# Component_Switch.net
KiCad netlist of a schematic drawn in Altium Designer
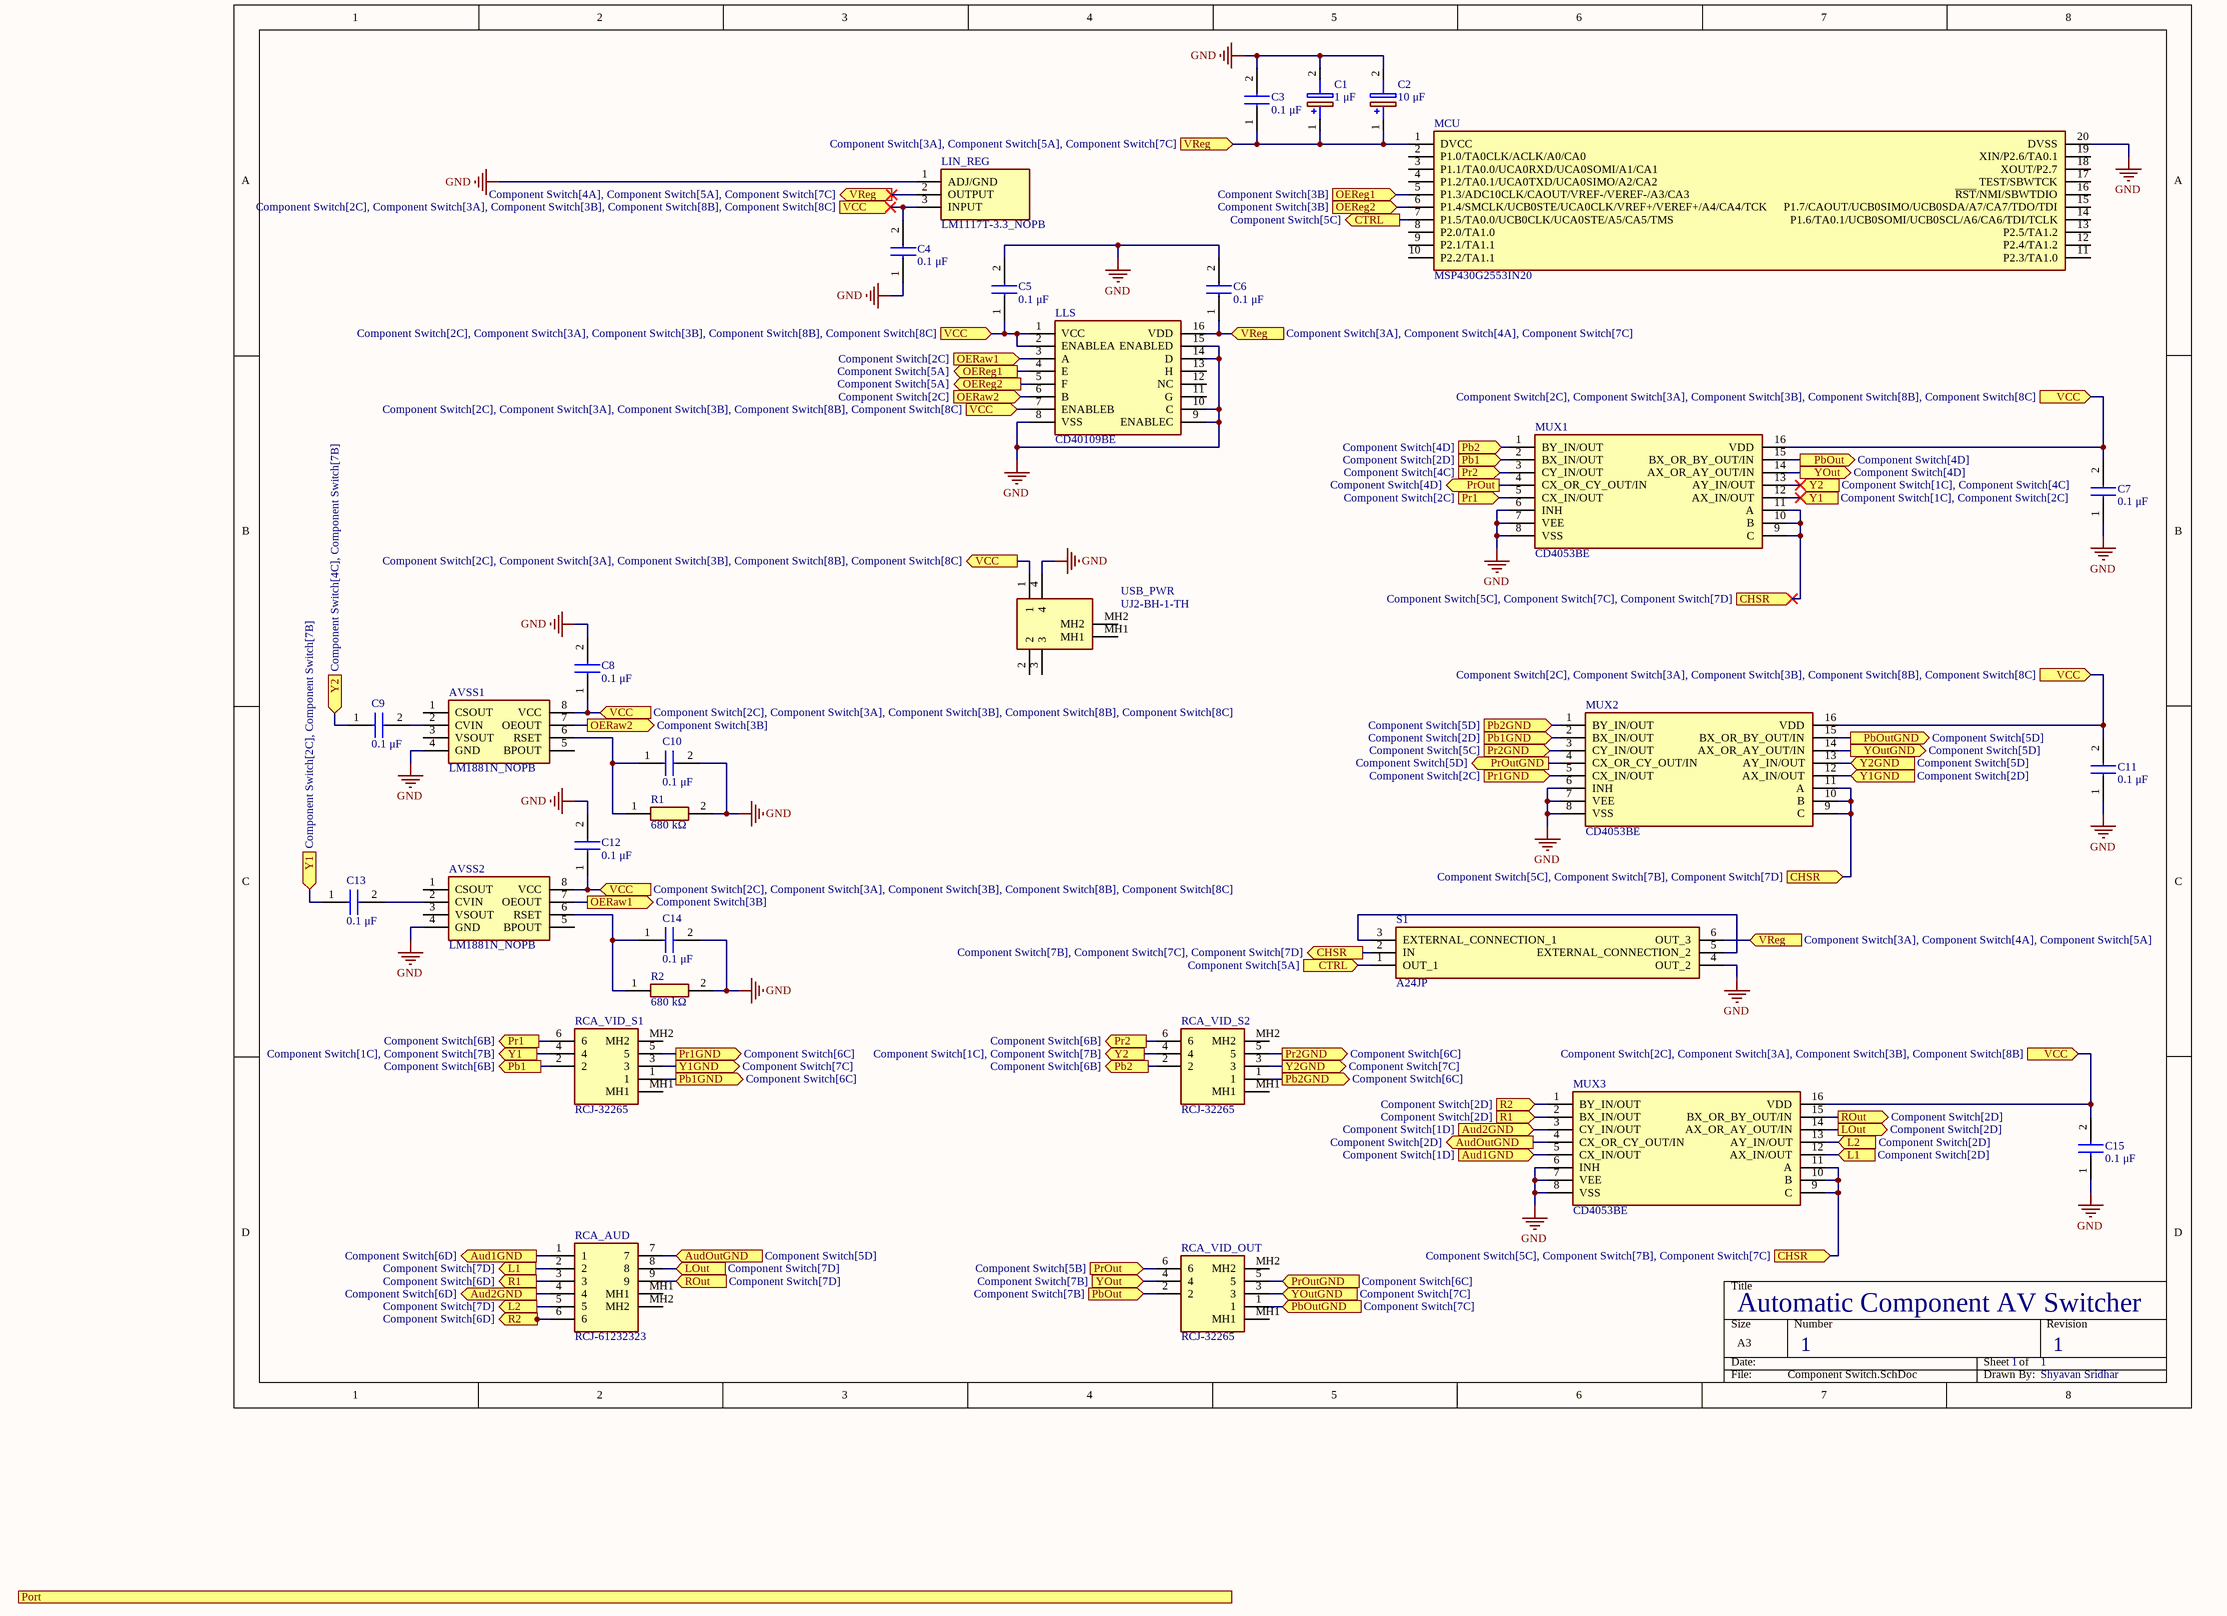
[diagram p0: Component Switch.SchDoc]

(export (version "E")
  (design (tool "Eeschema 10.0.6"))
  (components
    (comp (ref "AVSS1")
      (value "LM1881N_NOPB")
      (footprint "SamacSys:DIP794W53P254L959H508Q8N")
      (description "Integrated Circuit")
      (fields
        (field (name "MANUFACTURER_PART_NUMBER") "LM1881N/NOPB")
        (field (name "MOUSER PART NUMBER") "926-LM1881N/NOPB")
      )
      (libsource (lib "*") (part "LM1881N_NOPB"))
    )
    (comp (ref "AVSS2")
      (value "LM1881N_NOPB")
      (footprint "SamacSys:DIP794W53P254L959H508Q8N")
      (description "Integrated Circuit")
      (fields
        (field (name "MANUFACTURER_PART_NUMBER") "LM1881N/NOPB")
        (field (name "MOUSER PART NUMBER") "926-LM1881N/NOPB")
      )
      (libsource (lib "*") (part "LM1881N_NOPB"))
    )
    (comp (ref "C1")
      (value "1 μF")
      (footprint "SamacSys:CAPPRD200W52D500H1250")
      (description "Capacitor Polarised")
      (fields
        (field (name "MANUFACTURER_PART_NUMBER") "860020672005")
        (field (name "MOUSER PART NUMBER") "710-860020672005")
      )
      (libsource (lib "*") (part "860020672005"))
    )
    (comp (ref "C2")
      (value "10 μF")
      (footprint "SamacSys:CAPPRD200W52D500H1250")
      (description "Capacitor Polarised")
      (fields
        (field (name "MANUFACTURER_PART_NUMBER") "860020472003")
        (field (name "MOUSER PART NUMBER") "710-860020472003")
      )
      (libsource (lib "*") (part "860020472003"))
    )
    (comp (ref "C3")
      (value "0.1 μF")
      (footprint "SamacSys:C320C104K5R5TA")
      (description "Capacitor")
      (fields
        (field (name "MANUFACTURER_PART_NUMBER") "C320C104K5R5TA")
        (field (name "MOUSER PART NUMBER") "80-C320C104K5R")
      )
      (libsource (lib "*") (part "C320C104K5R5TA"))
    )
    (comp (ref "C4")
      (value "0.1 μF")
      (footprint "SamacSys:C320C104K5R5TA")
      (description "Capacitor")
      (fields
        (field (name "MANUFACTURER_PART_NUMBER") "C320C104K5R5TA")
        (field (name "MOUSER PART NUMBER") "80-C320C104K5R")
      )
      (libsource (lib "*") (part "C320C104K5R5TA"))
    )
    (comp (ref "C5")
      (value "0.1 μF")
      (footprint "SamacSys:C320C104K5R5TA")
      (description "Capacitor")
      (fields
        (field (name "MANUFACTURER_PART_NUMBER") "C320C104K5R5TA")
        (field (name "MOUSER PART NUMBER") "80-C320C104K5R")
      )
      (libsource (lib "*") (part "C320C104K5R5TA"))
    )
    (comp (ref "C6")
      (value "0.1 μF")
      (footprint "SamacSys:C320C104K5R5TA")
      (description "Capacitor")
      (fields
        (field (name "MANUFACTURER_PART_NUMBER") "C320C104K5R5TA")
        (field (name "MOUSER PART NUMBER") "80-C320C104K5R")
      )
      (libsource (lib "*") (part "C320C104K5R5TA"))
    )
    (comp (ref "C7")
      (value "0.1 μF")
      (footprint "SamacSys:C320C104K5R5TA")
      (description "Capacitor")
      (fields
        (field (name "MANUFACTURER_PART_NUMBER") "C320C104K5R5TA")
        (field (name "MOUSER PART NUMBER") "80-C320C104K5R")
      )
      (libsource (lib "*") (part "C320C104K5R5TA"))
    )
    (comp (ref "C8")
      (value "0.1 μF")
      (footprint "SamacSys:C320C104K5R5TA")
      (description "Capacitor")
      (fields
        (field (name "MANUFACTURER_PART_NUMBER") "C320C104K5R5TA")
        (field (name "MOUSER PART NUMBER") "80-C320C104K5R")
      )
      (libsource (lib "*") (part "C320C104K5R5TA"))
    )
    (comp (ref "C9")
      (value "0.1 μF")
      (footprint "SamacSys:C320C104K5R5TA")
      (description "Capacitor")
      (fields
        (field (name "MANUFACTURER_PART_NUMBER") "C320C104K5R5TA")
        (field (name "MOUSER PART NUMBER") "80-C320C104K5R")
      )
      (libsource (lib "*") (part "C320C104K5R5TA"))
    )
    (comp (ref "C10")
      (value "0.1 μF")
      (footprint "SamacSys:C320C104K5R5TA")
      (description "Capacitor")
      (fields
        (field (name "MANUFACTURER_PART_NUMBER") "C320C104K5R5TA")
        (field (name "MOUSER PART NUMBER") "80-C320C104K5R")
      )
      (libsource (lib "*") (part "C320C104K5R5TA"))
    )
    (comp (ref "C11")
      (value "0.1 μF")
      (footprint "SamacSys:C320C104K5R5TA")
      (description "Capacitor")
      (fields
        (field (name "MANUFACTURER_PART_NUMBER") "C320C104K5R5TA")
        (field (name "MOUSER PART NUMBER") "80-C320C104K5R")
      )
      (libsource (lib "*") (part "C320C104K5R5TA"))
    )
    (comp (ref "C12")
      (value "0.1 μF")
      (footprint "SamacSys:C320C104K5R5TA")
      (description "Capacitor")
      (fields
        (field (name "MANUFACTURER_PART_NUMBER") "C320C104K5R5TA")
        (field (name "MOUSER PART NUMBER") "80-C320C104K5R")
      )
      (libsource (lib "*") (part "C320C104K5R5TA"))
    )
    (comp (ref "C13")
      (value "0.1 μF")
      (footprint "SamacSys:C320C104K5R5TA")
      (description "Capacitor")
      (fields
        (field (name "MANUFACTURER_PART_NUMBER") "C320C104K5R5TA")
        (field (name "MOUSER PART NUMBER") "80-C320C104K5R")
      )
      (libsource (lib "*") (part "C320C104K5R5TA"))
    )
    (comp (ref "C14")
      (value "0.1 μF")
      (footprint "SamacSys:C320C104K5R5TA")
      (description "Capacitor")
      (fields
        (field (name "MANUFACTURER_PART_NUMBER") "C320C104K5R5TA")
        (field (name "MOUSER PART NUMBER") "80-C320C104K5R")
      )
      (libsource (lib "*") (part "C320C104K5R5TA"))
    )
    (comp (ref "C15")
      (value "0.1 μF")
      (footprint "SamacSys:C320C104K5R5TA")
      (description "Capacitor")
      (fields
        (field (name "MANUFACTURER_PART_NUMBER") "C320C104K5R5TA")
        (field (name "MOUSER PART NUMBER") "80-C320C104K5R")
      )
      (libsource (lib "*") (part "C320C104K5R5TA"))
    )
    (comp (ref "LIN_REG")
      (value "LM1117T-3.3_NOPB")
      (footprint "SamacSys:TO254P470X1028X1955-3P")
      (description "Integrated Circuit")
      (fields
        (field (name "MANUFACTURER_PART_NUMBER") "LM1117T-3.3/NOPB")
        (field (name "MOUSER PART NUMBER") "926-LM1117T-3.3/NOPB")
      )
      (libsource (lib "*") (part "LM1117T-3.3_NOPB"))
    )
    (comp (ref "LLS")
      (value "CD40109BE")
      (footprint "SamacSys:DIP794W53P254L1930H508Q16N")
      (description "Integrated Circuit")
      (fields (field (name "MOUSER PART NUMBER") "595-CD40109BE"))
      (libsource (lib "*") (part "CD40109BE"))
    )
    (comp (ref "MCU")
      (value "MSP430G2553IN20")
      (footprint "SamacSys:DIP794W53P254L2540H508Q20N")
      (description "Integrated Circuit")
      (fields (field (name "MOUSER PART NUMBER") "595-MSP430G2553IN20"))
      (libsource (lib "*") (part "MSP430G2553IN20"))
    )
    (comp (ref "MUX1")
      (value "CD4053BE")
      (footprint "SamacSys:DIP794W53P254L1930H508Q16N")
      (description "Integrated Circuit")
      (fields (field (name "MOUSER PART NUMBER") "595-CD4053BE"))
      (libsource (lib "*") (part "CD4053BE"))
    )
    (comp (ref "MUX2")
      (value "CD4053BE")
      (footprint "SamacSys:DIP794W53P254L1930H508Q16N")
      (description "Integrated Circuit")
      (fields (field (name "MOUSER PART NUMBER") "595-CD4053BE"))
      (libsource (lib "*") (part "CD4053BE"))
    )
    (comp (ref "MUX3")
      (value "CD4053BE")
      (footprint "SamacSys:DIP794W53P254L1930H508Q16N")
      (description "Integrated Circuit")
      (fields (field (name "MOUSER PART NUMBER") "595-CD4053BE"))
      (libsource (lib "*") (part "CD4053BE"))
    )
    (comp (ref "R1")
      (value "680 kΩ")
      (footprint "SamacSys:RESAD1520W63L600D230")
      (description "Resistor")
      (fields (field (name "MANUFACTURER_PART_NUMBER") "CF14JT680K"))
      (libsource (lib "*") (part "CF14JT680K"))
    )
    (comp (ref "R2")
      (value "680 kΩ")
      (footprint "SamacSys:RESAD1520W63L600D230")
      (description "Resistor")
      (fields (field (name "MANUFACTURER_PART_NUMBER") "CF14JT680K"))
      (libsource (lib "*") (part "CF14JT680K"))
    )
    (comp (ref "RCA_AUD")
      (value "RCJ-61232323")
      (footprint "SamacSys:RCJ61232323")
      (description "Connector")
      (fields (field (name "MOUSER PART NUMBER") "490-RCJ-61232323"))
      (libsource (lib "*") (part "RCJ-61232323"))
    )
    (comp (ref "RCA_VID_OUT")
      (value "RCJ-32265")
      (footprint "SamacSys:RCJ32265")
      (description "Connector")
      (fields (field (name "MOUSER PART NUMBER") "490-RCJ-32265"))
      (libsource (lib "*") (part "RCJ-32265"))
    )
    (comp (ref "RCA_VID_S1")
      (value "RCJ-32265")
      (footprint "SamacSys:RCJ32265")
      (description "Connector")
      (fields (field (name "MOUSER PART NUMBER") "490-RCJ-32265"))
      (libsource (lib "*") (part "RCJ-32265"))
    )
    (comp (ref "RCA_VID_S2")
      (value "RCJ-32265")
      (footprint "SamacSys:RCJ32265")
      (description "Connector")
      (fields (field (name "MOUSER PART NUMBER") "490-RCJ-32265"))
      (libsource (lib "*") (part "RCJ-32265"))
    )
    (comp (ref "S1")
      (value "A24JP")
      (footprint "SamacSys:A24JP")
      (description "Switch")
      (fields (field (name "MOUSER PART NUMBER") "633-A24JP"))
      (libsource (lib "*") (part "A24JP"))
    )
    (comp (ref "USB_PWR")
      (value "UJ2-BH-1-TH")
      (footprint "SamacSys:UJ2BH1TH")
      (description "Connector")
      (fields (field (name "MOUSER PART NUMBER") "490-UJ2-BH-1-TH"))
      (libsource (lib "*") (part "UJ2-BH-1-TH"))
    )
  )
  (nets
    (net (code "1") (name "/Aud1GND") (class "Default")
      (node (ref "MUX3") (pin "5") (pinfunction "CX_IN/OUT_5") (pintype "passive"))
      (node (ref "RCA_AUD") (pin "1") (pinfunction "1_1") (pintype "passive"))
    )
    (net (code "2") (name "/Aud2GND") (class "Default")
      (node (ref "MUX3") (pin "3") (pinfunction "CY_IN/OUT_3") (pintype "passive"))
      (node (ref "RCA_AUD") (pin "4") (pinfunction "4_4") (pintype "passive"))
    )
    (net (code "3") (name "/AudOutGND") (class "Default")
      (node (ref "MUX3") (pin "4") (pinfunction "CX_OR_CY_OUT/IN_4") (pintype "passive"))
      (node (ref "RCA_AUD") (pin "7") (pinfunction "7_7") (pintype "passive"))
    )
    (net (code "4") (name "/CHSR") (class "Default")
      (node (ref "MUX1") (pin "10") (pinfunction "B_10") (pintype "passive"))
      (node (ref "MUX1") (pin "11") (pinfunction "A_11") (pintype "passive"))
      (node (ref "MUX1") (pin "9") (pinfunction "C_9") (pintype "passive"))
      (node (ref "MUX2") (pin "10") (pinfunction "B_10") (pintype "passive"))
      (node (ref "MUX2") (pin "11") (pinfunction "A_11") (pintype "passive"))
      (node (ref "MUX2") (pin "9") (pinfunction "C_9") (pintype "passive"))
      (node (ref "MUX3") (pin "10") (pinfunction "B_10") (pintype "passive"))
      (node (ref "MUX3") (pin "11") (pinfunction "A_11") (pintype "passive"))
      (node (ref "MUX3") (pin "9") (pinfunction "C_9") (pintype "passive"))
      (node (ref "S1") (pin "2") (pinfunction "IN_2") (pintype "passive"))
    )
    (net (code "5") (name "/CTRL") (class "Default")
      (node (ref "MCU") (pin "7") (pinfunction "P1.5/TA0.0/UCB0CLK/UCA0STE/A5/CA5/TMS_7") (pintype "passive"))
      (node (ref "S1") (pin "1") (pinfunction "OUT_1_1") (pintype "passive"))
    )
    (net (code "6") (name "/L1") (class "Default")
      (node (ref "MUX3") (pin "12") (pinfunction "AX_IN/OUT_12") (pintype "passive"))
      (node (ref "RCA_AUD") (pin "2") (pinfunction "2_2") (pintype "passive"))
    )
    (net (code "7") (name "/L2") (class "Default")
      (node (ref "MUX3") (pin "13") (pinfunction "AY_IN/OUT_13") (pintype "passive"))
      (node (ref "RCA_AUD") (pin "5") (pinfunction "5_5") (pintype "passive"))
    )
    (net (code "8") (name "/LOut") (class "Default")
      (node (ref "MUX3") (pin "14") (pinfunction "AX_OR_AY_OUT/IN_14") (pintype "passive"))
      (node (ref "RCA_AUD") (pin "8") (pinfunction "8_8") (pintype "passive"))
    )
    (net (code "9") (name "/OERaw1") (class "Default")
      (node (ref "AVSS2") (pin "7") (pinfunction "OEOUT_7") (pintype "passive"))
      (node (ref "LLS") (pin "3") (pinfunction "A_3") (pintype "passive"))
    )
    (net (code "10") (name "/OERaw2") (class "Default")
      (node (ref "AVSS1") (pin "7") (pinfunction "OEOUT_7") (pintype "passive"))
      (node (ref "LLS") (pin "6") (pinfunction "B_6") (pintype "passive"))
    )
    (net (code "11") (name "/OEReg1") (class "Default")
      (node (ref "LLS") (pin "4") (pinfunction "E_4") (pintype "passive"))
      (node (ref "MCU") (pin "5") (pinfunction "P1.3/ADC10CLK/CAOUT/VREF-/VEREF-/A3/CA3_5") (pintype "passive"))
    )
    (net (code "12") (name "/OEReg2") (class "Default")
      (node (ref "LLS") (pin "5") (pinfunction "F_5") (pintype "passive"))
      (node (ref "MCU") (pin "6") (pinfunction "P1.4/SMCLK/UCB0STE/UCA0CLK/VREF+/VEREF+/A4/CA4/TCK_6") (pintype "passive"))
    )
    (net (code "13") (name "/Pb1") (class "Default")
      (node (ref "MUX1") (pin "2") (pinfunction "BX_IN/OUT_2") (pintype "passive"))
      (node (ref "RCA_VID_S1") (pin "2") (pinfunction "2_2") (pintype "passive"))
    )
    (net (code "14") (name "/Pb1GND") (class "Default")
      (node (ref "MUX2") (pin "2") (pinfunction "BX_IN/OUT_2") (pintype "passive"))
      (node (ref "RCA_VID_S1") (pin "1") (pinfunction "1_1") (pintype "passive"))
    )
    (net (code "15") (name "/Pb2") (class "Default")
      (node (ref "MUX1") (pin "1") (pinfunction "BY_IN/OUT_1") (pintype "passive"))
      (node (ref "RCA_VID_S2") (pin "2") (pinfunction "2_2") (pintype "passive"))
    )
    (net (code "16") (name "/Pb2GND") (class "Default")
      (node (ref "MUX2") (pin "1") (pinfunction "BY_IN/OUT_1") (pintype "passive"))
      (node (ref "RCA_VID_S2") (pin "1") (pinfunction "1_1") (pintype "passive"))
    )
    (net (code "17") (name "/PbOut") (class "Default")
      (node (ref "MUX1") (pin "15") (pinfunction "BX_OR_BY_OUT/IN_15") (pintype "passive"))
      (node (ref "RCA_VID_OUT") (pin "2") (pinfunction "2_2") (pintype "passive"))
    )
    (net (code "18") (name "/PbOutGND") (class "Default")
      (node (ref "MUX2") (pin "15") (pinfunction "BX_OR_BY_OUT/IN_15") (pintype "passive"))
      (node (ref "RCA_VID_OUT") (pin "1") (pinfunction "1_1") (pintype "passive"))
    )
    (net (code "20") (name "/Pr1") (class "Default")
      (node (ref "MUX1") (pin "5") (pinfunction "CX_IN/OUT_5") (pintype "passive"))
      (node (ref "RCA_VID_S1") (pin "6") (pinfunction "6_6") (pintype "passive"))
    )
    (net (code "21") (name "/Pr1GND") (class "Default")
      (node (ref "MUX2") (pin "5") (pinfunction "CX_IN/OUT_5") (pintype "passive"))
      (node (ref "RCA_VID_S1") (pin "5") (pinfunction "5_5") (pintype "passive"))
    )
    (net (code "22") (name "/Pr2") (class "Default")
      (node (ref "MUX1") (pin "3") (pinfunction "CY_IN/OUT_3") (pintype "passive"))
      (node (ref "RCA_VID_S2") (pin "6") (pinfunction "6_6") (pintype "passive"))
    )
    (net (code "23") (name "/Pr2GND") (class "Default")
      (node (ref "MUX2") (pin "3") (pinfunction "CY_IN/OUT_3") (pintype "passive"))
      (node (ref "RCA_VID_S2") (pin "5") (pinfunction "5_5") (pintype "passive"))
    )
    (net (code "24") (name "/PrOut") (class "Default")
      (node (ref "MUX1") (pin "4") (pinfunction "CX_OR_CY_OUT/IN_4") (pintype "passive"))
      (node (ref "RCA_VID_OUT") (pin "6") (pinfunction "6_6") (pintype "passive"))
    )
    (net (code "25") (name "/PrOutGND") (class "Default")
      (node (ref "MUX2") (pin "4") (pinfunction "CX_OR_CY_OUT/IN_4") (pintype "passive"))
      (node (ref "RCA_VID_OUT") (pin "5") (pinfunction "5_5") (pintype "passive"))
    )
    (net (code "26") (name "/R1") (class "Default")
      (node (ref "MUX3") (pin "2") (pinfunction "BX_IN/OUT_2") (pintype "passive"))
      (node (ref "RCA_AUD") (pin "3") (pinfunction "3_3") (pintype "passive"))
    )
    (net (code "27") (name "/R2") (class "Default")
      (node (ref "MUX3") (pin "1") (pinfunction "BY_IN/OUT_1") (pintype "passive"))
      (node (ref "RCA_AUD") (pin "6") (pinfunction "6_6") (pintype "passive"))
    )
    (net (code "28") (name "/ROut") (class "Default")
      (node (ref "MUX3") (pin "15") (pinfunction "BX_OR_BY_OUT/IN_15") (pintype "passive"))
      (node (ref "RCA_AUD") (pin "9") (pinfunction "9_9") (pintype "passive"))
    )
    (net (code "29") (name "/VCC") (class "Default")
      (node (ref "AVSS1") (pin "8") (pinfunction "VCC_8") (pintype "passive"))
      (node (ref "AVSS2") (pin "8") (pinfunction "VCC_8") (pintype "passive"))
      (node (ref "C11") (pin "2") (pinfunction "2_2") (pintype "passive"))
      (node (ref "C12") (pin "1") (pinfunction "1_1") (pintype "passive"))
      (node (ref "C15") (pin "2") (pinfunction "2_2") (pintype "passive"))
      (node (ref "C4") (pin "2") (pinfunction "2_2") (pintype "passive"))
      (node (ref "C5") (pin "1") (pinfunction "1_1") (pintype "passive"))
      (node (ref "C7") (pin "2") (pinfunction "2_2") (pintype "passive"))
      (node (ref "C8") (pin "1") (pinfunction "1_1") (pintype "passive"))
      (node (ref "LIN_REG") (pin "3") (pinfunction "INPUT_3") (pintype "passive"))
      (node (ref "LLS") (pin "1") (pinfunction "VCC_1") (pintype "power_in"))
      (node (ref "LLS") (pin "2") (pinfunction "ENABLEA_2") (pintype "passive"))
      (node (ref "LLS") (pin "7") (pinfunction "ENABLEB_7") (pintype "passive"))
      (node (ref "MUX1") (pin "16") (pinfunction "VDD_16") (pintype "passive"))
      (node (ref "MUX2") (pin "16") (pinfunction "VDD_16") (pintype "passive"))
      (node (ref "MUX3") (pin "16") (pinfunction "VDD_16") (pintype "passive"))
      (node (ref "USB_PWR") (pin "1") (pinfunction "1_1") (pintype "passive"))
    )
    (net (code "30") (name "/VReg") (class "Default")
      (node (ref "C1") (pin "1") (pinfunction "+_1") (pintype "passive"))
      (node (ref "C2") (pin "1") (pinfunction "+_1") (pintype "passive"))
      (node (ref "C3") (pin "1") (pinfunction "1_1") (pintype "passive"))
      (node (ref "C6") (pin "1") (pinfunction "1_1") (pintype "passive"))
      (node (ref "LIN_REG") (pin "2") (pinfunction "OUTPUT_2") (pintype "passive"))
      (node (ref "LLS") (pin "16") (pinfunction "VDD_16") (pintype "power_in"))
      (node (ref "MCU") (pin "1") (pinfunction "DVCC_1") (pintype "passive"))
      (node (ref "S1") (pin "6") (pinfunction "OUT_3_6") (pintype "passive"))
    )
    (net (code "31") (name "/Y1") (class "Default")
      (node (ref "C13") (pin "1") (pinfunction "1_1") (pintype "passive"))
      (node (ref "MUX1") (pin "12") (pinfunction "AX_IN/OUT_12") (pintype "passive"))
      (node (ref "RCA_VID_S1") (pin "4") (pinfunction "4_4") (pintype "passive"))
    )
    (net (code "32") (name "/Y1GND") (class "Default")
      (node (ref "MUX2") (pin "12") (pinfunction "AX_IN/OUT_12") (pintype "passive"))
      (node (ref "RCA_VID_S1") (pin "3") (pinfunction "3_3") (pintype "passive"))
    )
    (net (code "33") (name "/Y2") (class "Default")
      (node (ref "C9") (pin "1") (pinfunction "1_1") (pintype "passive"))
      (node (ref "MUX1") (pin "13") (pinfunction "AY_IN/OUT_13") (pintype "passive"))
      (node (ref "RCA_VID_S2") (pin "4") (pinfunction "4_4") (pintype "passive"))
    )
    (net (code "34") (name "/Y2GND") (class "Default")
      (node (ref "MUX2") (pin "13") (pinfunction "AY_IN/OUT_13") (pintype "passive"))
      (node (ref "RCA_VID_S2") (pin "3") (pinfunction "3_3") (pintype "passive"))
    )
    (net (code "35") (name "/YOut") (class "Default")
      (node (ref "MUX1") (pin "14") (pinfunction "AX_OR_AY_OUT/IN_14") (pintype "passive"))
      (node (ref "RCA_VID_OUT") (pin "4") (pinfunction "4_4") (pintype "passive"))
    )
    (net (code "36") (name "/YOutGND") (class "Default")
      (node (ref "MUX2") (pin "14") (pinfunction "AX_OR_AY_OUT/IN_14") (pintype "passive"))
      (node (ref "RCA_VID_OUT") (pin "3") (pinfunction "3_3") (pintype "passive"))
    )
    (net (code "37") (name "GND") (class "Default")
      (node (ref "AVSS1") (pin "4") (pinfunction "GND_4") (pintype "passive"))
      (node (ref "AVSS2") (pin "4") (pinfunction "GND_4") (pintype "passive"))
      (node (ref "C1") (pin "2") (pinfunction "-_2") (pintype "passive"))
      (node (ref "C10") (pin "2") (pinfunction "2_2") (pintype "passive"))
      (node (ref "C11") (pin "1") (pinfunction "1_1") (pintype "passive"))
      (node (ref "C12") (pin "2") (pinfunction "2_2") (pintype "passive"))
      (node (ref "C14") (pin "2") (pinfunction "2_2") (pintype "passive"))
      (node (ref "C15") (pin "1") (pinfunction "1_1") (pintype "passive"))
      (node (ref "C2") (pin "2") (pinfunction "-_2") (pintype "passive"))
      (node (ref "C3") (pin "2") (pinfunction "2_2") (pintype "passive"))
      (node (ref "C4") (pin "1") (pinfunction "1_1") (pintype "passive"))
      (node (ref "C5") (pin "2") (pinfunction "2_2") (pintype "passive"))
      (node (ref "C6") (pin "2") (pinfunction "2_2") (pintype "passive"))
      (node (ref "C7") (pin "1") (pinfunction "1_1") (pintype "passive"))
      (node (ref "C8") (pin "2") (pinfunction "2_2") (pintype "passive"))
      (node (ref "LIN_REG") (pin "1") (pinfunction "ADJ/GND_1") (pintype "passive"))
      (node (ref "LLS") (pin "10") (pinfunction "C_10") (pintype "passive"))
      (node (ref "LLS") (pin "14") (pinfunction "D_14") (pintype "passive"))
      (node (ref "LLS") (pin "15") (pinfunction "ENABLED_15") (pintype "passive"))
      (node (ref "LLS") (pin "8") (pinfunction "VSS_8") (pintype "power_in"))
      (node (ref "LLS") (pin "9") (pinfunction "ENABLEC_9") (pintype "passive"))
      (node (ref "MCU") (pin "20") (pinfunction "DVSS_20") (pintype "passive"))
      (node (ref "MUX1") (pin "6") (pinfunction "INH_6") (pintype "passive"))
      (node (ref "MUX1") (pin "7") (pinfunction "VEE_7") (pintype "passive"))
      (node (ref "MUX1") (pin "8") (pinfunction "VSS_8") (pintype "passive"))
      (node (ref "MUX2") (pin "6") (pinfunction "INH_6") (pintype "passive"))
      (node (ref "MUX2") (pin "7") (pinfunction "VEE_7") (pintype "passive"))
      (node (ref "MUX2") (pin "8") (pinfunction "VSS_8") (pintype "passive"))
      (node (ref "MUX3") (pin "6") (pinfunction "INH_6") (pintype "passive"))
      (node (ref "MUX3") (pin "7") (pinfunction "VEE_7") (pintype "passive"))
      (node (ref "MUX3") (pin "8") (pinfunction "VSS_8") (pintype "passive"))
      (node (ref "R1") (pin "2") (pinfunction "2_2") (pintype "passive"))
      (node (ref "R2") (pin "2") (pinfunction "2_2") (pintype "passive"))
      (node (ref "S1") (pin "4") (pinfunction "OUT_2_4") (pintype "passive"))
      (node (ref "USB_PWR") (pin "4") (pinfunction "4_4") (pintype "passive"))
    )
    (net (code "38") (name "Net-(AVSS1-CVIN)") (class "Default")
      (node (ref "AVSS1") (pin "2") (pinfunction "CVIN_2") (pintype "passive"))
      (node (ref "C9") (pin "2") (pinfunction "2_2") (pintype "passive"))
    )
    (net (code "39") (name "Net-(AVSS1-RSET)") (class "Default")
      (node (ref "AVSS1") (pin "6") (pinfunction "RSET_6") (pintype "passive"))
      (node (ref "C10") (pin "1") (pinfunction "1_1") (pintype "passive"))
      (node (ref "R1") (pin "1") (pinfunction "1_1") (pintype "passive"))
    )
    (net (code "40") (name "Net-(AVSS2-CVIN)") (class "Default")
      (node (ref "AVSS2") (pin "2") (pinfunction "CVIN_2") (pintype "passive"))
      (node (ref "C13") (pin "2") (pinfunction "2_2") (pintype "passive"))
    )
    (net (code "41") (name "Net-(AVSS2-RSET)") (class "Default")
      (node (ref "AVSS2") (pin "6") (pinfunction "RSET_6") (pintype "passive"))
      (node (ref "C14") (pin "1") (pinfunction "1_1") (pintype "passive"))
      (node (ref "R2") (pin "1") (pinfunction "1_1") (pintype "passive"))
    )
    (net (code "42") (name "Net-(S1-EXTERNAL_CONNECTION_1)") (class "Default")
      (node (ref "S1") (pin "3") (pinfunction "EXTERNAL_CONNECTION_1_3") (pintype "passive"))
      (node (ref "S1") (pin "5") (pinfunction "EXTERNAL_CONNECTION_2_5") (pintype "passive"))
    )
    (net (code "43") (name "unconnected-(AVSS1-BPOUT-Pad5)") (class "Default")
      (node (ref "AVSS1") (pin "5") (pinfunction "BPOUT_5") (pintype "passive"))
    )
    (net (code "44") (name "unconnected-(AVSS1-CSOUT-Pad1)") (class "Default")
      (node (ref "AVSS1") (pin "1") (pinfunction "CSOUT_1") (pintype "passive"))
    )
    (net (code "45") (name "unconnected-(AVSS1-VSOUT-Pad3)") (class "Default")
      (node (ref "AVSS1") (pin "3") (pinfunction "VSOUT_3") (pintype "passive"))
    )
    (net (code "46") (name "unconnected-(AVSS2-BPOUT-Pad5)") (class "Default")
      (node (ref "AVSS2") (pin "5") (pinfunction "BPOUT_5") (pintype "passive"))
    )
    (net (code "47") (name "unconnected-(AVSS2-CSOUT-Pad1)") (class "Default")
      (node (ref "AVSS2") (pin "1") (pinfunction "CSOUT_1") (pintype "passive"))
    )
    (net (code "48") (name "unconnected-(AVSS2-VSOUT-Pad3)") (class "Default")
      (node (ref "AVSS2") (pin "3") (pinfunction "VSOUT_3") (pintype "passive"))
    )
    (net (code "49") (name "unconnected-(LLS-G-Pad11)") (class "Default")
      (node (ref "LLS") (pin "11") (pinfunction "G_11") (pintype "passive"))
    )
    (net (code "50") (name "unconnected-(LLS-H-Pad13)") (class "Default")
      (node (ref "LLS") (pin "13") (pinfunction "H_13") (pintype "passive"))
    )
    (net (code "51") (name "unconnected-(LLS-NC-Pad12)") (class "Default")
      (node (ref "LLS") (pin "12") (pinfunction "NC_12") (pintype "passive"))
    )
    (net (code "52") (name "unconnected-(MCU-P1.0{slash}TA0CLK{slash}ACLK{slash}A0{slash}CA0-Pad2)") (class "Default")
      (node (ref "MCU") (pin "2") (pinfunction "P1.0/TA0CLK/ACLK/A0/CA0_2") (pintype "passive"))
    )
    (net (code "53") (name "unconnected-(MCU-P1.1{slash}TA0.0{slash}UCA0RXD{slash}UCA0SOMI{slash}A1{slash}CA1-Pad3)") (class "Default")
      (node (ref "MCU") (pin "3") (pinfunction "P1.1/TA0.0/UCA0RXD/UCA0SOMI/A1/CA1_3") (pintype "passive"))
    )
    (net (code "54") (name "unconnected-(MCU-P1.2{slash}TA0.1{slash}UCA0TXD{slash}UCA0SIMO{slash}A2{slash}CA2-Pad4)") (class "Default")
      (node (ref "MCU") (pin "4") (pinfunction "P1.2/TA0.1/UCA0TXD/UCA0SIMO/A2/CA2_4") (pintype "passive"))
    )
    (net (code "55") (name "unconnected-(MCU-P1.6{slash}TA0.1{slash}UCB0SOMI{slash}UCB0SCL{slash}A6{slash}CA6{slash}TDI{slash}TCLK-Pad14)") (class "Default")
      (node (ref "MCU") (pin "14") (pinfunction "P1.6/TA0.1/UCB0SOMI/UCB0SCL/A6/CA6/TDI/TCLK_14") (pintype "passive"))
    )
    (net (code "56") (name "unconnected-(MCU-P1.7{slash}CAOUT{slash}UCB0SIMO{slash}UCB0SDA{slash}A7{slash}CA7{slash}TDO{slash}TDI-Pad15)") (class "Default")
      (node (ref "MCU") (pin "15") (pinfunction "P1.7/CAOUT/UCB0SIMO/UCB0SDA/A7/CA7/TDO/TDI_15") (pintype "passive"))
    )
    (net (code "57") (name "unconnected-(MCU-P2.0{slash}TA1.0-Pad8)") (class "Default")
      (node (ref "MCU") (pin "8") (pinfunction "P2.0/TA1.0_8") (pintype "passive"))
    )
    (net (code "58") (name "unconnected-(MCU-P2.1{slash}TA1.1-Pad9)") (class "Default")
      (node (ref "MCU") (pin "9") (pinfunction "P2.1/TA1.1_9") (pintype "passive"))
    )
    (net (code "59") (name "unconnected-(MCU-P2.2{slash}TA1.1-Pad10)") (class "Default")
      (node (ref "MCU") (pin "10") (pinfunction "P2.2/TA1.1_10") (pintype "passive"))
    )
    (net (code "60") (name "unconnected-(MCU-P2.3{slash}TA1.0-Pad11)") (class "Default")
      (node (ref "MCU") (pin "11") (pinfunction "P2.3/TA1.0_11") (pintype "passive"))
    )
    (net (code "61") (name "unconnected-(MCU-P2.4{slash}TA1.2-Pad12)") (class "Default")
      (node (ref "MCU") (pin "12") (pinfunction "P2.4/TA1.2_12") (pintype "passive"))
    )
    (net (code "62") (name "unconnected-(MCU-P2.5{slash}TA1.2-Pad13)") (class "Default")
      (node (ref "MCU") (pin "13") (pinfunction "P2.5/TA1.2_13") (pintype "passive"))
    )
    (net (code "63") (name "unconnected-(MCU-TEST{slash}SBWTCK-Pad17)") (class "Default")
      (node (ref "MCU") (pin "17") (pinfunction "TEST/SBWTCK_17") (pintype "passive"))
    )
    (net (code "64") (name "unconnected-(MCU-XIN{slash}P2.6{slash}TA0.1-Pad19)") (class "Default")
      (node (ref "MCU") (pin "19") (pinfunction "XIN/P2.6/TA0.1_19") (pintype "passive"))
    )
    (net (code "65") (name "unconnected-(MCU-XOUT{slash}P2.7-Pad18)") (class "Default")
      (node (ref "MCU") (pin "18") (pinfunction "XOUT/P2.7_18") (pintype "passive"))
    )
    (net (code "66") (name "unconnected-(MCU-~{RST}{slash}NMI{slash}SBWTDIO-Pad16)") (class "Default")
      (node (ref "MCU") (pin "16") (pinfunction "~{RST}/NMI/SBWTDIO_16") (pintype "passive"))
    )
    (net (code "67") (name "unconnected-(RCA_AUD-PadMH1)") (class "Default")
      (node (ref "RCA_AUD") (pin "MH1") (pinfunction "MH1_MH1") (pintype "passive"))
    )
    (net (code "68") (name "unconnected-(RCA_AUD-PadMH2)") (class "Default")
      (node (ref "RCA_AUD") (pin "MH2") (pinfunction "MH2_MH2") (pintype "passive"))
    )
    (net (code "69") (name "unconnected-(RCA_VID_OUT-PadMH1)") (class "Default")
      (node (ref "RCA_VID_OUT") (pin "MH1") (pinfunction "MH1_MH1") (pintype "passive"))
    )
    (net (code "70") (name "unconnected-(RCA_VID_OUT-PadMH2)") (class "Default")
      (node (ref "RCA_VID_OUT") (pin "MH2") (pinfunction "MH2_MH2") (pintype "passive"))
    )
    (net (code "71") (name "unconnected-(RCA_VID_S1-PadMH1)") (class "Default")
      (node (ref "RCA_VID_S1") (pin "MH1") (pinfunction "MH1_MH1") (pintype "passive"))
    )
    (net (code "72") (name "unconnected-(RCA_VID_S1-PadMH2)") (class "Default")
      (node (ref "RCA_VID_S1") (pin "MH2") (pinfunction "MH2_MH2") (pintype "passive"))
    )
    (net (code "73") (name "unconnected-(RCA_VID_S2-PadMH1)") (class "Default")
      (node (ref "RCA_VID_S2") (pin "MH1") (pinfunction "MH1_MH1") (pintype "passive"))
    )
    (net (code "74") (name "unconnected-(RCA_VID_S2-PadMH2)") (class "Default")
      (node (ref "RCA_VID_S2") (pin "MH2") (pinfunction "MH2_MH2") (pintype "passive"))
    )
    (net (code "75") (name "unconnected-(USB_PWR-Pad2)") (class "Default")
      (node (ref "USB_PWR") (pin "2") (pinfunction "2_2") (pintype "passive"))
    )
    (net (code "76") (name "unconnected-(USB_PWR-Pad3)") (class "Default")
      (node (ref "USB_PWR") (pin "3") (pinfunction "3_3") (pintype "passive"))
    )
    (net (code "77") (name "unconnected-(USB_PWR-PadMH1)") (class "Default")
      (node (ref "USB_PWR") (pin "MH1") (pinfunction "MH1_MH1") (pintype "passive"))
    )
    (net (code "78") (name "unconnected-(USB_PWR-PadMH2)") (class "Default")
      (node (ref "USB_PWR") (pin "MH2") (pinfunction "MH2_MH2") (pintype "passive"))
    )
  )
)
